# Lamp3.net
KiCad netlist of a schematic drawn in EAGLE
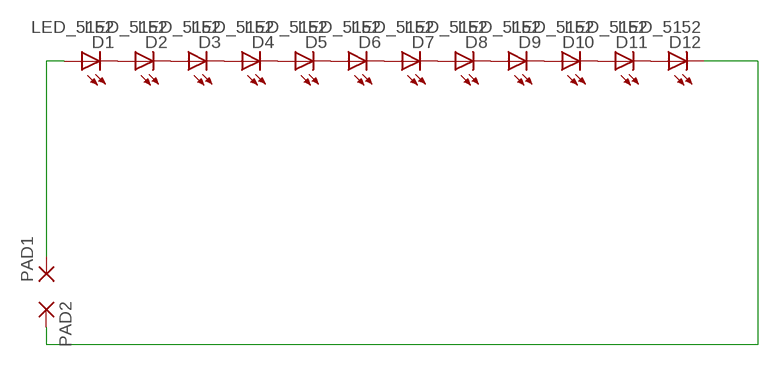
[diagram p0: schematic, sheet 1]

(export (version "E")
  (design (tool "Eeschema 10.0.6"))
  (components
    (comp (ref "D1")
      (value "LED_5152")
      (footprint "eagle-import:LED-5152")
      (libsource (lib "eagle-import") (part "LED_5152"))
    )
    (comp (ref "D2")
      (value "LED_5152")
      (footprint "eagle-import:LED-5152")
      (libsource (lib "eagle-import") (part "LED_5152"))
    )
    (comp (ref "D3")
      (value "LED_5152")
      (footprint "eagle-import:LED-5152")
      (libsource (lib "eagle-import") (part "LED_5152"))
    )
    (comp (ref "D4")
      (value "LED_5152")
      (footprint "eagle-import:LED-5152")
      (libsource (lib "eagle-import") (part "LED_5152"))
    )
    (comp (ref "D5")
      (value "LED_5152")
      (footprint "eagle-import:LED-5152")
      (libsource (lib "eagle-import") (part "LED_5152"))
    )
    (comp (ref "D6")
      (value "LED_5152")
      (footprint "eagle-import:LED-5152")
      (libsource (lib "eagle-import") (part "LED_5152"))
    )
    (comp (ref "D7")
      (value "LED_5152")
      (footprint "eagle-import:LED-5152")
      (libsource (lib "eagle-import") (part "LED_5152"))
    )
    (comp (ref "D8")
      (value "LED_5152")
      (footprint "eagle-import:LED-5152")
      (libsource (lib "eagle-import") (part "LED_5152"))
    )
    (comp (ref "D9")
      (value "LED_5152")
      (footprint "eagle-import:LED-5152")
      (libsource (lib "eagle-import") (part "LED_5152"))
    )
    (comp (ref "D10")
      (value "LED_5152")
      (footprint "eagle-import:LED-5152")
      (libsource (lib "eagle-import") (part "LED_5152"))
    )
    (comp (ref "D11")
      (value "LED_5152")
      (footprint "eagle-import:LED-5152")
      (libsource (lib "eagle-import") (part "LED_5152"))
    )
    (comp (ref "D12")
      (value "LED_5152")
      (footprint "eagle-import:LED-5152")
      (libsource (lib "eagle-import") (part "LED_5152"))
    )
    (comp (ref "PAD1")
      (value "SMD5")
      (footprint "eagle-import:SMD2,54-5,08")
      (libsource (lib "eagle-import") (part "SMD5"))
    )
    (comp (ref "PAD2")
      (value "SMD5")
      (footprint "eagle-import:SMD2,54-5,08")
      (libsource (lib "eagle-import") (part "SMD5"))
    )
  )
  (nets
    (net (code "1") (name "Net-(D1-PadC)") (class "Default")
      (node (ref "D1") (pin "C") (pinfunction "C_C") (pintype "passive"))
      (node (ref "D2") (pin "A") (pinfunction "A_A") (pintype "passive"))
    )
    (net (code "2") (name "Net-(D2-PadC)") (class "Default")
      (node (ref "D2") (pin "C") (pinfunction "C_C") (pintype "passive"))
      (node (ref "D3") (pin "A") (pinfunction "A_A") (pintype "passive"))
    )
    (net (code "3") (name "Net-(D3-PadC)") (class "Default")
      (node (ref "D3") (pin "C") (pinfunction "C_C") (pintype "passive"))
      (node (ref "D4") (pin "A") (pinfunction "A_A") (pintype "passive"))
    )
    (net (code "4") (name "Net-(D4-PadC)") (class "Default")
      (node (ref "D4") (pin "C") (pinfunction "C_C") (pintype "passive"))
      (node (ref "D5") (pin "A") (pinfunction "A_A") (pintype "passive"))
    )
    (net (code "5") (name "Net-(D5-PadC)") (class "Default")
      (node (ref "D5") (pin "C") (pinfunction "C_C") (pintype "passive"))
      (node (ref "D6") (pin "A") (pinfunction "A_A") (pintype "passive"))
    )
    (net (code "6") (name "Net-(D6-PadC)") (class "Default")
      (node (ref "D6") (pin "C") (pinfunction "C_C") (pintype "passive"))
      (node (ref "D7") (pin "A") (pinfunction "A_A") (pintype "passive"))
    )
    (net (code "7") (name "Net-(D7-PadC)") (class "Default")
      (node (ref "D7") (pin "C") (pinfunction "C_C") (pintype "passive"))
      (node (ref "D8") (pin "A") (pinfunction "A_A") (pintype "passive"))
    )
    (net (code "8") (name "Net-(D8-PadC)") (class "Default")
      (node (ref "D8") (pin "C") (pinfunction "C_C") (pintype "passive"))
      (node (ref "D9") (pin "A") (pinfunction "A_A") (pintype "passive"))
    )
    (net (code "9") (name "Net-(D10-PadA)") (class "Default")
      (node (ref "D10") (pin "A") (pinfunction "A_A") (pintype "passive"))
      (node (ref "D9") (pin "C") (pinfunction "C_C") (pintype "passive"))
    )
    (net (code "10") (name "Net-(D10-PadC)") (class "Default")
      (node (ref "D10") (pin "C") (pinfunction "C_C") (pintype "passive"))
      (node (ref "D11") (pin "A") (pinfunction "A_A") (pintype "passive"))
    )
    (net (code "11") (name "Net-(D11-PadC)") (class "Default")
      (node (ref "D11") (pin "C") (pinfunction "C_C") (pintype "passive"))
      (node (ref "D12") (pin "A") (pinfunction "A_A") (pintype "passive"))
    )
    (net (code "12") (name "Net-(PAD1-P)") (class "Default")
      (node (ref "D1") (pin "A") (pinfunction "A_A") (pintype "passive"))
      (node (ref "PAD1") (pin "1") (pinfunction "P_1") (pintype "passive"))
    )
    (net (code "13") (name "Net-(PAD2-P)") (class "Default")
      (node (ref "D12") (pin "C") (pinfunction "C_C") (pintype "passive"))
      (node (ref "PAD2") (pin "1") (pinfunction "P_1") (pintype "passive"))
    )
  )
)
